# i2c_adc_avr.net
KiCad netlist of a schematic drawn in EAGLE
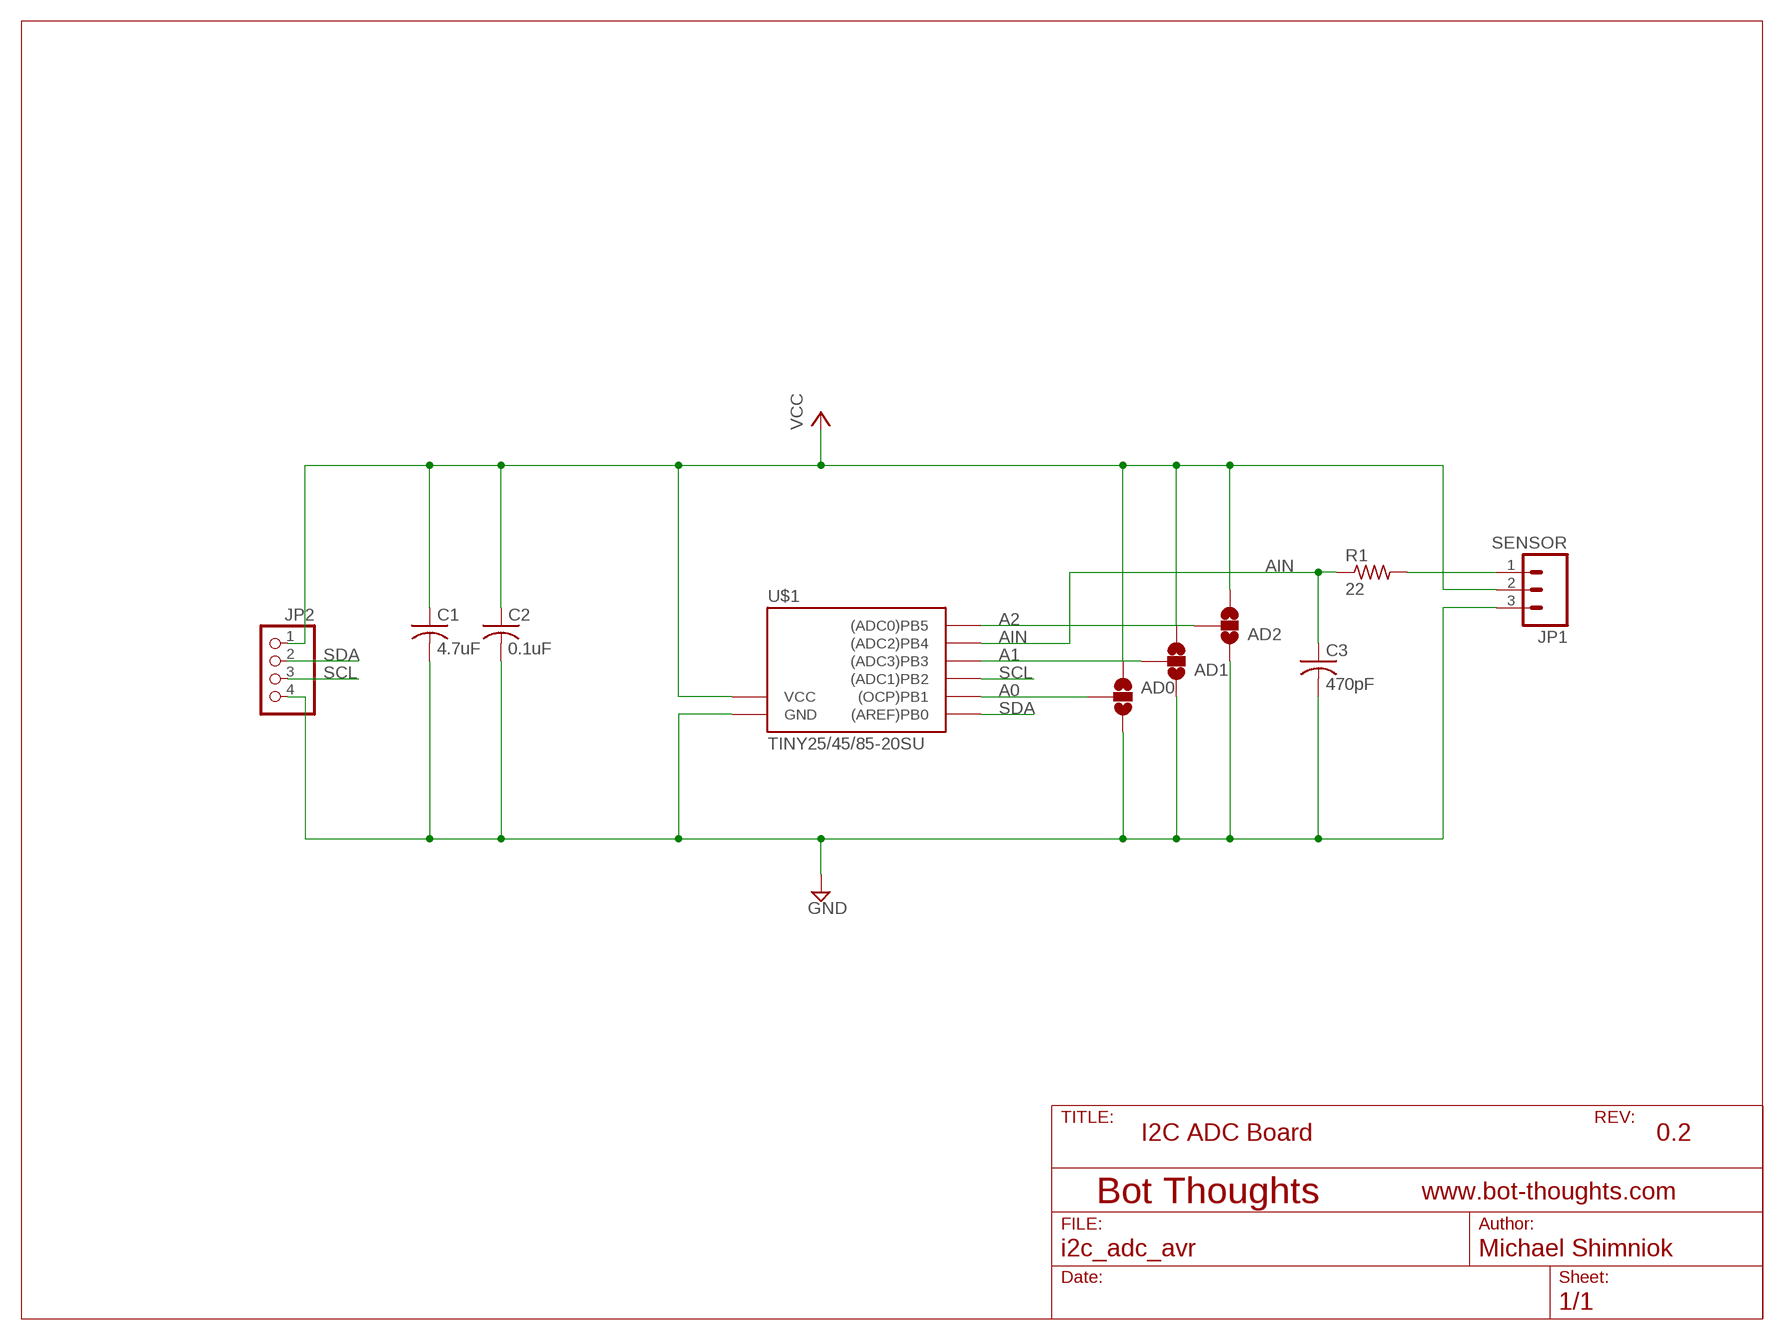
[diagram p0: schematic, sheet 1]

(export (version "E")
  (design (tool "Eeschema 10.0.6"))
  (components
    (comp (ref "AD0")
      (value "SOLDERJUMPER_2WAYS")
      (footprint "eagle-import:SJ_3")
      (libsource (lib "eagle-import") (part "SOLDERJUMPER_2WAYS"))
    )
    (comp (ref "AD1")
      (value "SOLDERJUMPER_2WAYS")
      (footprint "eagle-import:SJ_3")
      (libsource (lib "eagle-import") (part "SOLDERJUMPER_2WAYS"))
    )
    (comp (ref "AD2")
      (value "SOLDERJUMPER_2WAYS")
      (footprint "eagle-import:SJ_3")
      (libsource (lib "eagle-import") (part "SOLDERJUMPER_2WAYS"))
    )
    (comp (ref "C1")
      (value "4.7uF")
      (footprint "eagle-import:C0603")
      (libsource (lib "eagle-import") (part "C-USC0603"))
    )
    (comp (ref "C2")
      (value "0.1uF")
      (footprint "eagle-import:C0603")
      (libsource (lib "eagle-import") (part "C-USC0603"))
    )
    (comp (ref "C3")
      (value "470pF")
      (footprint "eagle-import:C0603")
      (libsource (lib "eagle-import") (part "C-USC0603"))
    )
    (comp (ref "JP1")
      (value "SENSOR")
      (footprint "eagle-import:1X03")
      (libsource (lib "eagle-import") (part "M03PTH"))
    )
    (comp (ref "JP2")
      (value "PINHD-1X04_2.54-S")
      (footprint "eagle-import:1X04-S")
      (libsource (lib "eagle-import") (part "PINHD-1X04_2.54-S"))
    )
    (comp (ref "R1")
      (value "22")
      (footprint "eagle-import:R0603")
      (libsource (lib "eagle-import") (part "R-US_R0603"))
    )
    (comp (ref "U$1")
      (value "TINY25/45/85-20SU")
      (footprint "eagle-import:SOIC8")
      (libsource (lib "eagle-import") (part "TINY25/45/85-20SU"))
    )
  )
  (nets
    (net (code "1") (name "/A0") (class "Default")
      (node (ref "AD0") (pin "2") (pinfunction "2_2") (pintype "passive"))
      (node (ref "U$1") (pin "6") (pinfunction "(OCP)PB1_6") (pintype "bidirectional"))
    )
    (net (code "2") (name "/A1") (class "Default")
      (node (ref "AD1") (pin "2") (pinfunction "2_2") (pintype "passive"))
      (node (ref "U$1") (pin "2") (pinfunction "(ADC3)PB3_2") (pintype "bidirectional"))
    )
    (net (code "3") (name "/A2") (class "Default")
      (node (ref "AD2") (pin "2") (pinfunction "2_2") (pintype "passive"))
      (node (ref "U$1") (pin "1") (pinfunction "(ADC0)PB5_1") (pintype "bidirectional"))
    )
    (net (code "4") (name "/AIN") (class "Default")
      (node (ref "C3") (pin "1") (pinfunction "1_1") (pintype "passive"))
      (node (ref "R1") (pin "1") (pinfunction "1_1") (pintype "passive"))
      (node (ref "U$1") (pin "3") (pinfunction "(ADC2)PB4_3") (pintype "bidirectional"))
    )
    (net (code "5") (name "/SCL") (class "Default")
      (node (ref "JP2") (pin "3") (pinfunction "3_3") (pintype "passive"))
      (node (ref "U$1") (pin "7") (pinfunction "(ADC1)PB2_7") (pintype "bidirectional"))
    )
    (net (code "6") (name "/SDA") (class "Default")
      (node (ref "JP2") (pin "2") (pinfunction "2_2") (pintype "passive"))
      (node (ref "U$1") (pin "5") (pinfunction "(AREF)PB0_5") (pintype "bidirectional"))
    )
    (net (code "7") (name "GND") (class "Default")
      (node (ref "AD0") (pin "3") (pinfunction "3_3") (pintype "passive"))
      (node (ref "AD1") (pin "1") (pinfunction "1_1") (pintype "passive"))
      (node (ref "AD2") (pin "1") (pinfunction "1_1") (pintype "passive"))
      (node (ref "C1") (pin "2") (pinfunction "2_2") (pintype "passive"))
      (node (ref "C2") (pin "2") (pinfunction "2_2") (pintype "passive"))
      (node (ref "C3") (pin "2") (pinfunction "2_2") (pintype "passive"))
      (node (ref "JP1") (pin "3") (pinfunction "3_3") (pintype "passive"))
      (node (ref "JP2") (pin "4") (pinfunction "4_4") (pintype "passive"))
      (node (ref "U$1") (pin "4") (pinfunction "GND_4") (pintype "power_in"))
    )
    (net (code "8") (name "Net-(JP1-Pad1)") (class "Default")
      (node (ref "JP1") (pin "1") (pinfunction "1_1") (pintype "passive"))
      (node (ref "R1") (pin "2") (pinfunction "2_2") (pintype "passive"))
    )
    (net (code "9") (name "VCC") (class "Default")
      (node (ref "AD0") (pin "1") (pinfunction "1_1") (pintype "passive"))
      (node (ref "AD1") (pin "3") (pinfunction "3_3") (pintype "passive"))
      (node (ref "AD2") (pin "3") (pinfunction "3_3") (pintype "passive"))
      (node (ref "C1") (pin "1") (pinfunction "1_1") (pintype "passive"))
      (node (ref "C2") (pin "1") (pinfunction "1_1") (pintype "passive"))
      (node (ref "JP1") (pin "2") (pinfunction "2_2") (pintype "passive"))
      (node (ref "JP2") (pin "1") (pinfunction "1_1") (pintype "passive"))
      (node (ref "U$1") (pin "8") (pinfunction "VCC_8") (pintype "power_in"))
    )
  )
)
